# main_module.net
KiCad netlist of a schematic drawn in EAGLE
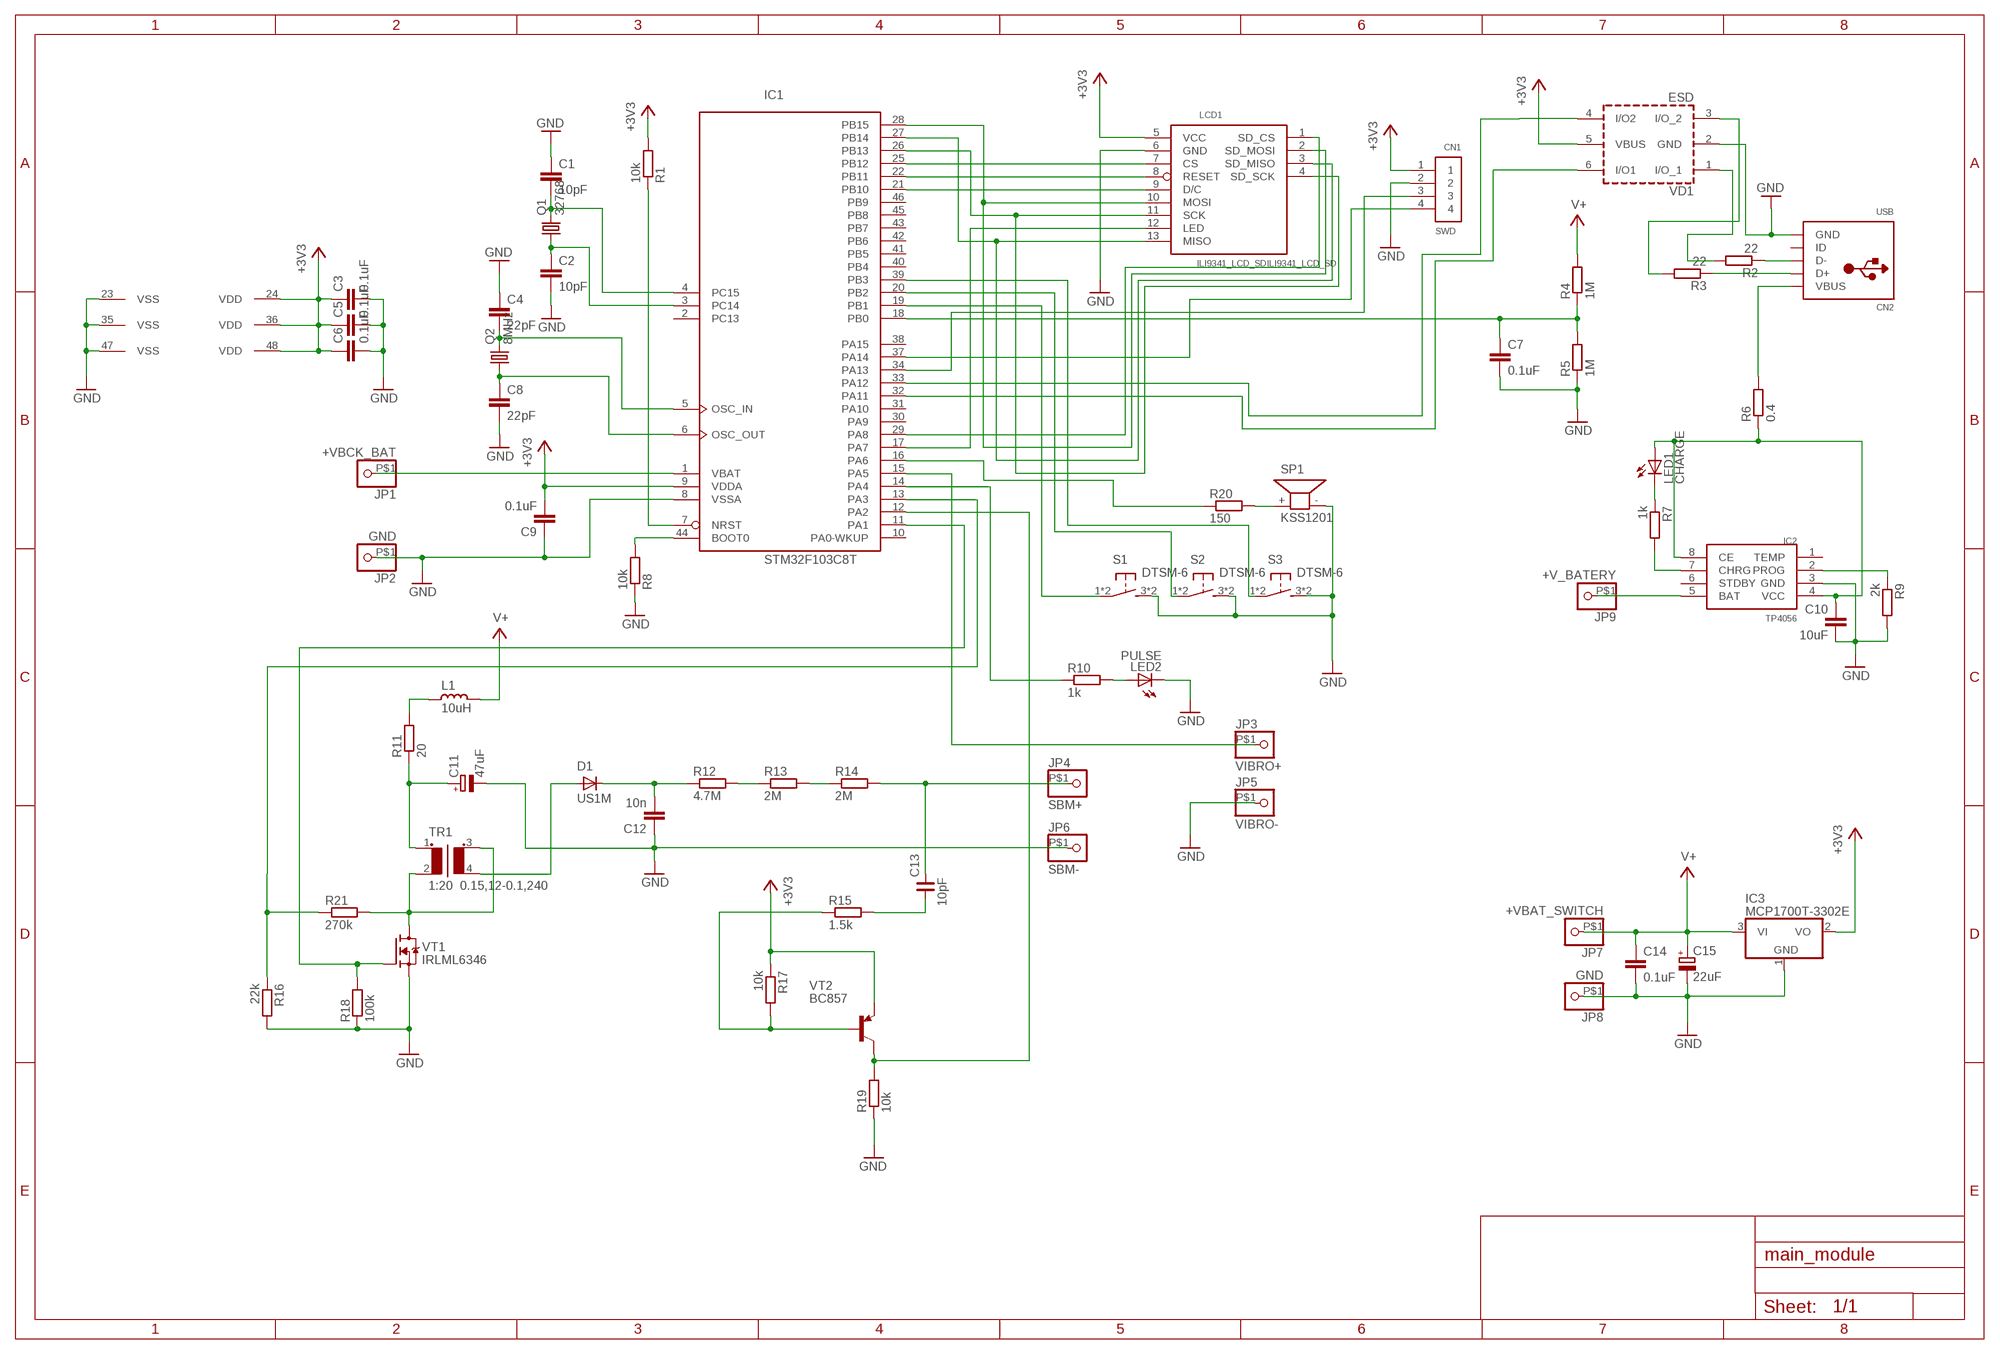
[diagram p0: schematic, sheet 1]

(export (version "E")
  (design (tool "Eeschema 10.0.6"))
  (components
    (comp (ref "C1")
      (value "10pF")
      (footprint "eagle-import:C0805")
      (libsource (lib "eagle-import") (part "C-EUC0805"))
    )
    (comp (ref "C2")
      (value "10pF")
      (footprint "eagle-import:C0805")
      (libsource (lib "eagle-import") (part "C-EUC0805"))
    )
    (comp (ref "C3")
      (value "0.1uF")
      (footprint "eagle-import:C0805")
      (libsource (lib "eagle-import") (part "C-EUC0805"))
    )
    (comp (ref "C4")
      (value "22pF")
      (footprint "eagle-import:C0805")
      (libsource (lib "eagle-import") (part "C-EUC0805"))
    )
    (comp (ref "C5")
      (value "0.1uF")
      (footprint "eagle-import:C0805")
      (libsource (lib "eagle-import") (part "C-EUC0805"))
    )
    (comp (ref "C6")
      (value "0.1uF")
      (footprint "eagle-import:C0805")
      (libsource (lib "eagle-import") (part "C-EUC0805"))
    )
    (comp (ref "C7")
      (value "0.1uF")
      (footprint "eagle-import:C0805")
      (libsource (lib "eagle-import") (part "C-EUC0805"))
    )
    (comp (ref "C8")
      (value "22pF")
      (footprint "eagle-import:C0805")
      (libsource (lib "eagle-import") (part "C-EUC0805"))
    )
    (comp (ref "C9")
      (value "0.1uF")
      (footprint "eagle-import:C0805")
      (libsource (lib "eagle-import") (part "C-EUC0805"))
    )
    (comp (ref "C10")
      (value "10uF")
      (footprint "eagle-import:C0805")
      (libsource (lib "eagle-import") (part "C-EUC0805"))
    )
    (comp (ref "C11")
      (value "47uF")
      (footprint "eagle-import:C_6032-28R")
      (libsource (lib "eagle-import") (part "CPOL-EUC/6032-28R"))
    )
    (comp (ref "C12")
      (value "10n")
      (footprint "eagle-import:C1206")
      (libsource (lib "eagle-import") (part "C-EUC1206"))
    )
    (comp (ref "C13")
      (value "10pF")
      (footprint "eagle-import:C1206")
      (libsource (lib "eagle-import") (part "C_1206"))
    )
    (comp (ref "C14")
      (value "0.1uF")
      (footprint "eagle-import:C0805")
      (libsource (lib "eagle-import") (part "C-EUC0805"))
    )
    (comp (ref "C15")
      (value "22uF")
      (footprint "eagle-import:C_6032-28R")
      (libsource (lib "eagle-import") (part "CPOL-EUC/6032-28R"))
    )
    (comp (ref "CN1")
      (value "SWD")
      (footprint "eagle-import:1X04-BIG")
      (libsource (lib "eagle-import") (part "1X4-BIG"))
    )
    (comp (ref "CN2")
      (value "USB")
      (footprint "eagle-import:USB-MINIB")
      (libsource (lib "eagle-import") (part "USBMINIB"))
    )
    (comp (ref "D1")
      (value "US1M")
      (footprint "eagle-import:SMA-DO214AC")
      (libsource (lib "eagle-import") (part "GF1"))
    )
    (comp (ref "IC1")
      (value "STM32F103C8T")
      (footprint "eagle-import:LQFP48")
      (libsource (lib "eagle-import") (part "STM32F103CT8"))
    )
    (comp (ref "IC2")
      (value "TP4056")
      (footprint "eagle-import:SOP-8")
      (libsource (lib "eagle-import") (part "TP4056"))
    )
    (comp (ref "IC3")
      (value "MCP1700T-3302E")
      (footprint "eagle-import:SOT23")
      (libsource (lib "eagle-import") (part "MCP1703CB"))
    )
    (comp (ref "JP1")
      (value "+VBCK_BAT")
      (footprint "eagle-import:1X1-BIGPOGO")
      (libsource (lib "eagle-import") (part "PINHD-1X1-BIGPOGO"))
    )
    (comp (ref "JP2")
      (value "GND")
      (footprint "eagle-import:1X1-BIGPOGO")
      (libsource (lib "eagle-import") (part "PINHD-1X1-BIGPOGO"))
    )
    (comp (ref "JP3")
      (value "VIBRO+")
      (footprint "eagle-import:1X1-BIGPOGO")
      (libsource (lib "eagle-import") (part "PINHD-1X1-BIGPOGO"))
    )
    (comp (ref "JP4")
      (value "SBM+")
      (footprint "eagle-import:1X1-BIGPOGO")
      (libsource (lib "eagle-import") (part "PINHD-1X1-BIGPOGO"))
    )
    (comp (ref "JP5")
      (value "VIBRO-")
      (footprint "eagle-import:1X1-BIGPOGO")
      (libsource (lib "eagle-import") (part "PINHD-1X1-BIGPOGO"))
    )
    (comp (ref "JP6")
      (value "SBM-")
      (footprint "eagle-import:1X1-BIGPOGO")
      (libsource (lib "eagle-import") (part "PINHD-1X1-BIGPOGO"))
    )
    (comp (ref "JP7")
      (value "+VBAT_SWITCH")
      (footprint "eagle-import:1X1-BIGPOGO")
      (libsource (lib "eagle-import") (part "PINHD-1X1-BIGPOGO"))
    )
    (comp (ref "JP8")
      (value "GND")
      (footprint "eagle-import:1X1-BIGPOGO")
      (libsource (lib "eagle-import") (part "PINHD-1X1-BIGPOGO"))
    )
    (comp (ref "JP9")
      (value "+V_BATERY")
      (footprint "eagle-import:1X1-BIGPOGO")
      (libsource (lib "eagle-import") (part "PINHD-1X1-BIGPOGO"))
    )
    (comp (ref "L1")
      (value "10uH")
      (footprint "eagle-import:L0805")
      (libsource (lib "eagle-import") (part "L_0805"))
    )
    (comp (ref "LCD1")
      (value "ILI9341_LCD_SDILI9341_LCD_SD")
      (footprint "eagle-import:ILI9341_LCD_SD")
      (libsource (lib "eagle-import") (part "ILI9341_LCD_SDILI9341_LCD_SD"))
    )
    (comp (ref "LED1")
      (value "CHARGE")
      (footprint "eagle-import:CHIP-LED0805")
      (libsource (lib "eagle-import") (part "led_LEDCHIP-LED0805"))
    )
    (comp (ref "LED2")
      (value "PULSE")
      (footprint "eagle-import:LED3MM")
      (libsource (lib "eagle-import") (part "LED3MM"))
    )
    (comp (ref "Q1")
      (value "32768")
      (footprint "eagle-import:HC49_S")
      (libsource (lib "eagle-import") (part "CRYSTALHC49S"))
    )
    (comp (ref "Q2")
      (value "8MHz")
      (footprint "eagle-import:HC49_S")
      (libsource (lib "eagle-import") (part "CRYSTALHC49S"))
    )
    (comp (ref "R1")
      (value "10k")
      (footprint "eagle-import:M0805")
      (libsource (lib "eagle-import") (part "R-EU_M0805"))
    )
    (comp (ref "R2")
      (value "22")
      (footprint "eagle-import:M0805")
      (libsource (lib "eagle-import") (part "R-EU_M0805"))
    )
    (comp (ref "R3")
      (value "22")
      (footprint "eagle-import:M0805")
      (libsource (lib "eagle-import") (part "R-EU_M0805"))
    )
    (comp (ref "R4")
      (value "1M")
      (footprint "eagle-import:M0805")
      (libsource (lib "eagle-import") (part "R-EU_M0805"))
    )
    (comp (ref "R5")
      (value "1M")
      (footprint "eagle-import:M0805")
      (libsource (lib "eagle-import") (part "R-EU_M0805"))
    )
    (comp (ref "R6")
      (value "0.4")
      (footprint "eagle-import:M1206")
      (libsource (lib "eagle-import") (part "R-EU_M1206"))
    )
    (comp (ref "R7")
      (value "1k")
      (footprint "eagle-import:M0805")
      (libsource (lib "eagle-import") (part "R-EU_M0805"))
    )
    (comp (ref "R8")
      (value "10k")
      (footprint "eagle-import:M0805")
      (libsource (lib "eagle-import") (part "R-EU_M0805"))
    )
    (comp (ref "R9")
      (value "2k")
      (footprint "eagle-import:M0805")
      (libsource (lib "eagle-import") (part "R-EU_M0805"))
    )
    (comp (ref "R10")
      (value "1k")
      (footprint "eagle-import:M0805")
      (libsource (lib "eagle-import") (part "R-EU_M0805"))
    )
    (comp (ref "R11")
      (value "20")
      (footprint "eagle-import:M0805")
      (libsource (lib "eagle-import") (part "R-EU_M0805"))
    )
    (comp (ref "R12")
      (value "4.7M")
      (footprint "eagle-import:M0805")
      (libsource (lib "eagle-import") (part "R-EU_M0805"))
    )
    (comp (ref "R13")
      (value "2M")
      (footprint "eagle-import:M0805")
      (libsource (lib "eagle-import") (part "R-EU_M0805"))
    )
    (comp (ref "R14")
      (value "2M")
      (footprint "eagle-import:M0805")
      (libsource (lib "eagle-import") (part "R-EU_M0805"))
    )
    (comp (ref "R15")
      (value "1.5k")
      (footprint "eagle-import:M0805")
      (libsource (lib "eagle-import") (part "R-EU_M0805"))
    )
    (comp (ref "R16")
      (value "22k")
      (footprint "eagle-import:M0805")
      (libsource (lib "eagle-import") (part "R-EU_M0805"))
    )
    (comp (ref "R17")
      (value "10k")
      (footprint "eagle-import:M0805")
      (libsource (lib "eagle-import") (part "R-EU_M0805"))
    )
    (comp (ref "R18")
      (value "100k")
      (footprint "eagle-import:M0805")
      (libsource (lib "eagle-import") (part "R-EU_M0805"))
    )
    (comp (ref "R19")
      (value "10k")
      (footprint "eagle-import:M0805")
      (libsource (lib "eagle-import") (part "R-EU_M0805"))
    )
    (comp (ref "R20")
      (value "150")
      (footprint "eagle-import:M0805")
      (libsource (lib "eagle-import") (part "R-EU_M0805"))
    )
    (comp (ref "R21")
      (value "270k")
      (footprint "eagle-import:M0805")
      (libsource (lib "eagle-import") (part "R-EU_M0805"))
    )
    (comp (ref "S1")
      (value "DTSM-6")
      (footprint "eagle-import:DTSM-6")
      (libsource (lib "eagle-import") (part "DTSM-6"))
    )
    (comp (ref "S2")
      (value "DTSM-6")
      (footprint "eagle-import:DTSM-6")
      (libsource (lib "eagle-import") (part "DTSM-6"))
    )
    (comp (ref "S3")
      (value "DTSM-6")
      (footprint "eagle-import:DTSM-6")
      (libsource (lib "eagle-import") (part "DTSM-6"))
    )
    (comp (ref "SP1")
      (value "KSS1201")
      (footprint "eagle-import:KSS1201")
      (libsource (lib "eagle-import") (part "KSS1201"))
    )
    (comp (ref "TR1")
      (value "1:20 0.15,12-0.1,240")
      (footprint "eagle-import:RING-TRANS")
      (libsource (lib "eagle-import") (part "RING-TRANS"))
    )
    (comp (ref "VD1")
      (value "ESD")
      (footprint "eagle-import:SOT-23-6L")
      (libsource (lib "eagle-import") (part "USBLC6-2SC6"))
    )
    (comp (ref "VT1")
      (value "IRLML6346")
      (footprint "eagle-import:SOT23")
      (libsource (lib "eagle-import") (part "MOSFET-N-SOT23"))
    )
    (comp (ref "VT2")
      (value "BC857")
      (footprint "eagle-import:SOT23-BCE")
      (libsource (lib "eagle-import") (part "-PNP-SOT23-BCE"))
    )
  )
  (nets
    (net (code "1") (name "+3V3") (class "Default")
      (node (ref "C3") (pin "1") (pinfunction "1_1") (pintype "passive"))
      (node (ref "C5") (pin "1") (pinfunction "1_1") (pintype "passive"))
      (node (ref "C6") (pin "1") (pinfunction "1_1") (pintype "passive"))
      (node (ref "C9") (pin "2") (pinfunction "2_2") (pintype "passive"))
      (node (ref "CN1") (pin "1") (pinfunction "1_1") (pintype "bidirectional"))
      (node (ref "IC1") (pin "24") (pinfunction "VDD_24") (pintype "power_in"))
      (node (ref "IC1") (pin "36") (pinfunction "VDD_36") (pintype "power_in"))
      (node (ref "IC1") (pin "48") (pinfunction "VDD_48") (pintype "power_in"))
      (node (ref "IC1") (pin "9") (pinfunction "VDDA_9") (pintype "power_in"))
      (node (ref "IC3") (pin "2") (pinfunction "VO_2") (pintype "passive"))
      (node (ref "LCD1") (pin "5") (pinfunction "VCC_5") (pintype "power_in"))
      (node (ref "R1") (pin "2") (pinfunction "2_2") (pintype "passive"))
      (node (ref "R17") (pin "1") (pinfunction "1_1") (pintype "passive"))
      (node (ref "VD1") (pin "5") (pinfunction "VBUS_5") (pintype "bidirectional"))
      (node (ref "VT2") (pin "E") (pinfunction "E_E") (pintype "passive"))
    )
    (net (code "2") (name "GND") (class "Default")
      (node (ref "C1") (pin "1") (pinfunction "1_1") (pintype "passive"))
      (node (ref "C10") (pin "2") (pinfunction "2_2") (pintype "passive"))
      (node (ref "C11") (pin "-") (pinfunction "-_-") (pintype "passive"))
      (node (ref "C12") (pin "1") (pinfunction "1_1") (pintype "passive"))
      (node (ref "C14") (pin "2") (pinfunction "2_2") (pintype "passive"))
      (node (ref "C15") (pin "-") (pinfunction "-_-") (pintype "passive"))
      (node (ref "C2") (pin "2") (pinfunction "2_2") (pintype "passive"))
      (node (ref "C3") (pin "2") (pinfunction "2_2") (pintype "passive"))
      (node (ref "C4") (pin "1") (pinfunction "1_1") (pintype "passive"))
      (node (ref "C5") (pin "2") (pinfunction "2_2") (pintype "passive"))
      (node (ref "C6") (pin "2") (pinfunction "2_2") (pintype "passive"))
      (node (ref "C7") (pin "2") (pinfunction "2_2") (pintype "passive"))
      (node (ref "C8") (pin "2") (pinfunction "2_2") (pintype "passive"))
      (node (ref "C9") (pin "1") (pinfunction "1_1") (pintype "passive"))
      (node (ref "CN1") (pin "2") (pinfunction "2_2") (pintype "bidirectional"))
      (node (ref "CN2") (pin "GND") (pinfunction "GND_GND") (pintype "power_in"))
      (node (ref "IC1") (pin "23") (pinfunction "VSS_23") (pintype "power_in"))
      (node (ref "IC1") (pin "35") (pinfunction "VSS_35") (pintype "power_in"))
      (node (ref "IC1") (pin "47") (pinfunction "VSS_47") (pintype "power_in"))
      (node (ref "IC1") (pin "8") (pinfunction "VSSA_8") (pintype "power_in"))
      (node (ref "IC2") (pin "3") (pinfunction "GND_3") (pintype "bidirectional"))
      (node (ref "IC3") (pin "1") (pinfunction "GND_1") (pintype "passive"))
      (node (ref "JP2") (pin "P$1") (pinfunction "1_P$1") (pintype "passive"))
      (node (ref "JP5") (pin "P$1") (pinfunction "1_P$1") (pintype "passive"))
      (node (ref "JP6") (pin "P$1") (pinfunction "1_P$1") (pintype "passive"))
      (node (ref "JP8") (pin "P$1") (pinfunction "1_P$1") (pintype "passive"))
      (node (ref "LCD1") (pin "6") (pinfunction "GND_6") (pintype "power_in"))
      (node (ref "LED2") (pin "K") (pinfunction "C_K") (pintype "passive"))
      (node (ref "R16") (pin "2") (pinfunction "2_2") (pintype "passive"))
      (node (ref "R18") (pin "1") (pinfunction "1_1") (pintype "passive"))
      (node (ref "R19") (pin "1") (pinfunction "1_1") (pintype "passive"))
      (node (ref "R5") (pin "1") (pinfunction "1_1") (pintype "passive"))
      (node (ref "R8") (pin "1") (pinfunction "1_1") (pintype "passive"))
      (node (ref "R9") (pin "2") (pinfunction "2_2") (pintype "passive"))
      (node (ref "S1") (pin "3") (pinfunction "3_3") (pintype "passive"))
      (node (ref "S1") (pin "4") (pinfunction "3_4") (pintype "passive"))
      (node (ref "S2") (pin "3") (pinfunction "3_3") (pintype "passive"))
      (node (ref "S2") (pin "4") (pinfunction "3_4") (pintype "passive"))
      (node (ref "S3") (pin "3") (pinfunction "3_3") (pintype "passive"))
      (node (ref "S3") (pin "4") (pinfunction "3_4") (pintype "passive"))
      (node (ref "SP1") (pin "-") (pinfunction "2_-") (pintype "passive"))
      (node (ref "VD1") (pin "2") (pinfunction "GND_2") (pintype "bidirectional"))
      (node (ref "VT1") (pin "2") (pinfunction "S_2") (pintype "passive"))
    )
    (net (code "3") (name "Net-(C13-Pad1)") (class "Default")
      (node (ref "C13") (pin "1") (pinfunction "1_1") (pintype "passive"))
      (node (ref "R15") (pin "2") (pinfunction "2_2") (pintype "passive"))
    )
    (net (code "4") (name "Net-(CN2-PadD+)") (class "Default")
      (node (ref "CN2") (pin "D+") (pinfunction "D+_D+") (pintype "bidirectional"))
      (node (ref "R3") (pin "1") (pinfunction "1_1") (pintype "passive"))
    )
    (net (code "5") (name "Net-(CN2-PadD-)") (class "Default")
      (node (ref "CN2") (pin "D-") (pinfunction "D-_D-") (pintype "bidirectional"))
      (node (ref "R2") (pin "1") (pinfunction "1_1") (pintype "passive"))
    )
    (net (code "6") (name "Net-(CN2-PadVBUS)") (class "Default")
      (node (ref "CN2") (pin "VBUS") (pinfunction "VBUS_VBUS") (pintype "power_in"))
      (node (ref "R6") (pin "2") (pinfunction "2_2") (pintype "passive"))
    )
    (net (code "7") (name "Net-(D1-C)") (class "Default")
      (node (ref "C12") (pin "2") (pinfunction "2_2") (pintype "passive"))
      (node (ref "D1") (pin "K") (pinfunction "C_K") (pintype "passive"))
      (node (ref "R12") (pin "1") (pinfunction "1_1") (pintype "passive"))
    )
    (net (code "8") (name "Net-(IC1A-BOOT0)") (class "Default")
      (node (ref "IC1") (pin "44") (pinfunction "BOOT0_44") (pintype "input"))
      (node (ref "R8") (pin "2") (pinfunction "2_2") (pintype "passive"))
    )
    (net (code "9") (name "Net-(IC1A-NRST)") (class "Default")
      (node (ref "IC1") (pin "7") (pinfunction "NRST_7") (pintype "bidirectional"))
      (node (ref "R1") (pin "1") (pinfunction "1_1") (pintype "passive"))
    )
    (net (code "10") (name "Net-(IC1A-OSC_IN)") (class "Default")
      (node (ref "C4") (pin "2") (pinfunction "2_2") (pintype "passive"))
      (node (ref "IC1") (pin "5") (pinfunction "OSC_IN_5") (pintype "bidirectional"))
      (node (ref "Q2") (pin "2") (pinfunction "2_2") (pintype "passive"))
    )
    (net (code "11") (name "Net-(IC1A-OSC_OUT)") (class "Default")
      (node (ref "C8") (pin "1") (pinfunction "1_1") (pintype "passive"))
      (node (ref "IC1") (pin "6") (pinfunction "OSC_OUT_6") (pintype "bidirectional"))
      (node (ref "Q2") (pin "1") (pinfunction "1_1") (pintype "passive"))
    )
    (net (code "12") (name "Net-(IC1A-PA1)") (class "Default")
      (node (ref "IC1") (pin "11") (pinfunction "PA1_11") (pintype "bidirectional"))
      (node (ref "R18") (pin "2") (pinfunction "2_2") (pintype "passive"))
      (node (ref "VT1") (pin "1") (pinfunction "G_1") (pintype "passive"))
    )
    (net (code "13") (name "Net-(IC1A-PA2)") (class "Default")
      (node (ref "IC1") (pin "12") (pinfunction "PA2_12") (pintype "bidirectional"))
      (node (ref "R19") (pin "2") (pinfunction "2_2") (pintype "passive"))
      (node (ref "VT2") (pin "C") (pinfunction "C_C") (pintype "passive"))
    )
    (net (code "14") (name "Net-(IC1A-PA3)") (class "Default")
      (node (ref "IC1") (pin "13") (pinfunction "PA3_13") (pintype "bidirectional"))
      (node (ref "R16") (pin "1") (pinfunction "1_1") (pintype "passive"))
      (node (ref "R21") (pin "1") (pinfunction "1_1") (pintype "passive"))
    )
    (net (code "15") (name "Net-(IC1A-PA4)") (class "Default")
      (node (ref "IC1") (pin "14") (pinfunction "PA4_14") (pintype "bidirectional"))
      (node (ref "R10") (pin "1") (pinfunction "1_1") (pintype "passive"))
    )
    (net (code "16") (name "Net-(IC1A-PA5)") (class "Default")
      (node (ref "IC1") (pin "15") (pinfunction "PA5_15") (pintype "bidirectional"))
      (node (ref "JP3") (pin "P$1") (pinfunction "1_P$1") (pintype "passive"))
    )
    (net (code "17") (name "Net-(IC1A-PA6)") (class "Default")
      (node (ref "IC1") (pin "16") (pinfunction "PA6_16") (pintype "bidirectional"))
      (node (ref "R20") (pin "1") (pinfunction "1_1") (pintype "passive"))
    )
    (net (code "18") (name "Net-(IC1A-PA7)") (class "Default")
      (node (ref "IC1") (pin "17") (pinfunction "PA7_17") (pintype "bidirectional"))
      (node (ref "LCD1") (pin "12") (pinfunction "LED_12") (pintype "input"))
    )
    (net (code "19") (name "Net-(IC1A-PA8)") (class "Default")
      (node (ref "IC1") (pin "29") (pinfunction "PA8_29") (pintype "bidirectional"))
      (node (ref "LCD1") (pin "1") (pinfunction "SD_CS_1") (pintype "input"))
    )
    (net (code "20") (name "Net-(IC1A-PA11)") (class "Default")
      (node (ref "IC1") (pin "32") (pinfunction "PA11_32") (pintype "bidirectional"))
      (node (ref "VD1") (pin "6") (pinfunction "I/O1_6") (pintype "bidirectional"))
    )
    (net (code "21") (name "Net-(IC1A-PA12)") (class "Default")
      (node (ref "IC1") (pin "33") (pinfunction "PA12_33") (pintype "bidirectional"))
      (node (ref "VD1") (pin "4") (pinfunction "I/O2_4") (pintype "bidirectional"))
    )
    (net (code "22") (name "Net-(IC1A-PA13)") (class "Default")
      (node (ref "CN1") (pin "3") (pinfunction "3_3") (pintype "bidirectional"))
      (node (ref "IC1") (pin "34") (pinfunction "PA13_34") (pintype "bidirectional"))
    )
    (net (code "23") (name "Net-(IC1A-PA14)") (class "Default")
      (node (ref "CN1") (pin "4") (pinfunction "4_4") (pintype "bidirectional"))
      (node (ref "IC1") (pin "37") (pinfunction "PA14_37") (pintype "bidirectional"))
    )
    (net (code "24") (name "Net-(IC1A-PB0)") (class "Default")
      (node (ref "C7") (pin "1") (pinfunction "1_1") (pintype "passive"))
      (node (ref "IC1") (pin "18") (pinfunction "PB0_18") (pintype "bidirectional"))
      (node (ref "R4") (pin "1") (pinfunction "1_1") (pintype "passive"))
      (node (ref "R5") (pin "2") (pinfunction "2_2") (pintype "passive"))
    )
    (net (code "25") (name "Net-(IC1A-PB1)") (class "Default")
      (node (ref "IC1") (pin "19") (pinfunction "PB1_19") (pintype "bidirectional"))
      (node (ref "S1") (pin "1") (pinfunction "1_1") (pintype "passive"))
      (node (ref "S1") (pin "2") (pinfunction "1_2") (pintype "passive"))
    )
    (net (code "26") (name "Net-(IC1A-PB2)") (class "Default")
      (node (ref "IC1") (pin "20") (pinfunction "PB2_20") (pintype "bidirectional"))
      (node (ref "S2") (pin "1") (pinfunction "1_1") (pintype "passive"))
      (node (ref "S2") (pin "2") (pinfunction "1_2") (pintype "passive"))
    )
    (net (code "27") (name "Net-(IC1A-PB3)") (class "Default")
      (node (ref "IC1") (pin "39") (pinfunction "PB3_39") (pintype "bidirectional"))
      (node (ref "S3") (pin "1") (pinfunction "1_1") (pintype "passive"))
      (node (ref "S3") (pin "2") (pinfunction "1_2") (pintype "passive"))
    )
    (net (code "28") (name "Net-(IC1A-PB10)") (class "Default")
      (node (ref "IC1") (pin "21") (pinfunction "PB10_21") (pintype "bidirectional"))
      (node (ref "LCD1") (pin "9") (pinfunction "D/C_9") (pintype "input"))
    )
    (net (code "29") (name "Net-(IC1A-PB11)") (class "Default")
      (node (ref "IC1") (pin "22") (pinfunction "PB11_22") (pintype "bidirectional"))
      (node (ref "LCD1") (pin "8") (pinfunction "RESET_8") (pintype "input"))
    )
    (net (code "30") (name "Net-(IC1A-PB12)") (class "Default")
      (node (ref "IC1") (pin "25") (pinfunction "PB12_25") (pintype "bidirectional"))
      (node (ref "LCD1") (pin "7") (pinfunction "CS_7") (pintype "input"))
    )
    (net (code "31") (name "Net-(IC1A-PB13)") (class "Default")
      (node (ref "IC1") (pin "26") (pinfunction "PB13_26") (pintype "bidirectional"))
      (node (ref "LCD1") (pin "11") (pinfunction "SCK_11") (pintype "input"))
      (node (ref "LCD1") (pin "4") (pinfunction "SD_SCK_4") (pintype "input"))
    )
    (net (code "32") (name "Net-(IC1A-PB14)") (class "Default")
      (node (ref "IC1") (pin "27") (pinfunction "PB14_27") (pintype "bidirectional"))
      (node (ref "LCD1") (pin "13") (pinfunction "MISO_13") (pintype "bidirectional"))
      (node (ref "LCD1") (pin "3") (pinfunction "SD_MISO_3") (pintype "bidirectional"))
    )
    (net (code "33") (name "Net-(IC1A-PB15)") (class "Default")
      (node (ref "IC1") (pin "28") (pinfunction "PB15_28") (pintype "bidirectional"))
      (node (ref "LCD1") (pin "10") (pinfunction "MOSI_10") (pintype "bidirectional"))
      (node (ref "LCD1") (pin "2") (pinfunction "SD_MOSI_2") (pintype "bidirectional"))
    )
    (net (code "34") (name "Net-(IC1A-PC14)") (class "Default")
      (node (ref "C2") (pin "1") (pinfunction "1_1") (pintype "passive"))
      (node (ref "IC1") (pin "3") (pinfunction "PC14_3") (pintype "bidirectional"))
      (node (ref "Q1") (pin "1") (pinfunction "1_1") (pintype "passive"))
    )
    (net (code "35") (name "Net-(IC1A-PC15)") (class "Default")
      (node (ref "C1") (pin "2") (pinfunction "2_2") (pintype "passive"))
      (node (ref "IC1") (pin "4") (pinfunction "PC15_4") (pintype "bidirectional"))
      (node (ref "Q1") (pin "2") (pinfunction "2_2") (pintype "passive"))
    )
    (net (code "36") (name "Net-(IC1A-VBAT)") (class "Default")
      (node (ref "IC1") (pin "1") (pinfunction "VBAT_1") (pintype "power_in"))
      (node (ref "JP1") (pin "P$1") (pinfunction "1_P$1") (pintype "passive"))
    )
    (net (code "37") (name "Net-(IC2-BAT)") (class "Default")
      (node (ref "IC2") (pin "5") (pinfunction "BAT_5") (pintype "bidirectional"))
      (node (ref "JP9") (pin "P$1") (pinfunction "1_P$1") (pintype "passive"))
    )
    (net (code "38") (name "Net-(IC2-CE)") (class "Default")
      (node (ref "C10") (pin "1") (pinfunction "1_1") (pintype "passive"))
      (node (ref "IC2") (pin "4") (pinfunction "VCC_4") (pintype "bidirectional"))
      (node (ref "IC2") (pin "8") (pinfunction "CE_8") (pintype "bidirectional"))
      (node (ref "LED1") (pin "A") (pinfunction "A_A") (pintype "passive"))
      (node (ref "R6") (pin "1") (pinfunction "1_1") (pintype "passive"))
    )
    (net (code "39") (name "Net-(IC2-CHRG)") (class "Default")
      (node (ref "IC2") (pin "7") (pinfunction "CHRG_7") (pintype "bidirectional"))
      (node (ref "R7") (pin "2") (pinfunction "2_2") (pintype "passive"))
    )
    (net (code "40") (name "Net-(IC2-PROG)") (class "Default")
      (node (ref "IC2") (pin "2") (pinfunction "PROG_2") (pintype "bidirectional"))
      (node (ref "R9") (pin "1") (pinfunction "1_1") (pintype "passive"))
    )
    (net (code "41") (name "Net-(JP4-1)") (class "Default")
      (node (ref "C13") (pin "2") (pinfunction "2_2") (pintype "passive"))
      (node (ref "JP4") (pin "P$1") (pinfunction "1_P$1") (pintype "passive"))
      (node (ref "R14") (pin "2") (pinfunction "2_2") (pintype "passive"))
    )
    (net (code "42") (name "Net-(L1-Pad2)") (class "Default")
      (node (ref "L1") (pin "2") (pinfunction "2_2") (pintype "passive"))
      (node (ref "R11") (pin "2") (pinfunction "2_2") (pintype "passive"))
    )
    (net (code "43") (name "Net-(LED1-PadC)") (class "Default")
      (node (ref "LED1") (pin "C") (pinfunction "C_C") (pintype "passive"))
      (node (ref "R7") (pin "1") (pinfunction "1_1") (pintype "passive"))
    )
    (net (code "44") (name "Net-(LED2-PadA)") (class "Default")
      (node (ref "LED2") (pin "A") (pinfunction "A_A") (pintype "passive"))
      (node (ref "R10") (pin "2") (pinfunction "2_2") (pintype "passive"))
    )
    (net (code "45") (name "Net-(R12-Pad2)") (class "Default")
      (node (ref "R12") (pin "2") (pinfunction "2_2") (pintype "passive"))
      (node (ref "R13") (pin "1") (pinfunction "1_1") (pintype "passive"))
    )
    (net (code "46") (name "Net-(R13-Pad2)") (class "Default")
      (node (ref "R13") (pin "2") (pinfunction "2_2") (pintype "passive"))
      (node (ref "R14") (pin "1") (pinfunction "1_1") (pintype "passive"))
    )
    (net (code "47") (name "Net-(R15-Pad1)") (class "Default")
      (node (ref "R15") (pin "1") (pinfunction "1_1") (pintype "passive"))
      (node (ref "R17") (pin "2") (pinfunction "2_2") (pintype "passive"))
      (node (ref "VT2") (pin "B") (pinfunction "B_B") (pintype "passive"))
    )
    (net (code "48") (name "Net-(SP1-1)") (class "Default")
      (node (ref "R20") (pin "2") (pinfunction "2_2") (pintype "passive"))
      (node (ref "SP1") (pin "+") (pinfunction "1_+") (pintype "passive"))
    )
    (net (code "49") (name "Net-(TR1-P1)") (class "Default")
      (node (ref "C11") (pin "+") (pinfunction "+_+") (pintype "passive"))
      (node (ref "R11") (pin "1") (pinfunction "1_1") (pintype "passive"))
      (node (ref "TR1") (pin "1") (pinfunction "P1_1") (pintype "passive"))
    )
    (net (code "50") (name "Net-(TR1-P2)") (class "Default")
      (node (ref "R21") (pin "2") (pinfunction "2_2") (pintype "passive"))
      (node (ref "TR1") (pin "2") (pinfunction "P2_2") (pintype "passive"))
      (node (ref "TR1") (pin "3") (pinfunction "S1_3") (pintype "passive"))
      (node (ref "VT1") (pin "3") (pinfunction "D_3") (pintype "passive"))
    )
    (net (code "51") (name "Net-(TR1-S2)") (class "Default")
      (node (ref "D1") (pin "A") (pinfunction "A_A") (pintype "passive"))
      (node (ref "TR1") (pin "4") (pinfunction "S2_4") (pintype "passive"))
    )
    (net (code "52") (name "Net-(VD1-I{slash}O_1)") (class "Default")
      (node (ref "R2") (pin "2") (pinfunction "2_2") (pintype "passive"))
      (node (ref "VD1") (pin "1") (pinfunction "I/O_1_1") (pintype "bidirectional"))
    )
    (net (code "53") (name "Net-(VD1-I{slash}O_2)") (class "Default")
      (node (ref "R3") (pin "2") (pinfunction "2_2") (pintype "passive"))
      (node (ref "VD1") (pin "3") (pinfunction "I/O_2_3") (pintype "bidirectional"))
    )
    (net (code "54") (name "V+") (class "Default")
      (node (ref "C14") (pin "1") (pinfunction "1_1") (pintype "passive"))
      (node (ref "C15") (pin "+") (pinfunction "+_+") (pintype "passive"))
      (node (ref "IC3") (pin "3") (pinfunction "VI_3") (pintype "input"))
      (node (ref "JP7") (pin "P$1") (pinfunction "1_P$1") (pintype "passive"))
      (node (ref "L1") (pin "1") (pinfunction "1_1") (pintype "passive"))
      (node (ref "R4") (pin "2") (pinfunction "2_2") (pintype "passive"))
    )
    (net (code "55") (name "unconnected-(CN2-PadID)") (class "Default")
      (node (ref "CN2") (pin "ID") (pinfunction "ID_ID") (pintype "bidirectional"))
    )
    (net (code "56") (name "unconnected-(IC1A-PA0-WKUP-Pad10)") (class "Default")
      (node (ref "IC1") (pin "10") (pinfunction "PA0-WKUP_10") (pintype "bidirectional"))
    )
    (net (code "57") (name "unconnected-(IC1A-PA9-Pad30)") (class "Default")
      (node (ref "IC1") (pin "30") (pinfunction "PA9_30") (pintype "bidirectional"))
    )
    (net (code "58") (name "unconnected-(IC1A-PA10-Pad31)") (class "Default")
      (node (ref "IC1") (pin "31") (pinfunction "PA10_31") (pintype "bidirectional"))
    )
    (net (code "59") (name "unconnected-(IC1A-PA15-Pad38)") (class "Default")
      (node (ref "IC1") (pin "38") (pinfunction "PA15_38") (pintype "bidirectional"))
    )
    (net (code "60") (name "unconnected-(IC1A-PB4-Pad40)") (class "Default")
      (node (ref "IC1") (pin "40") (pinfunction "PB4_40") (pintype "bidirectional"))
    )
    (net (code "61") (name "unconnected-(IC1A-PB5-Pad41)") (class "Default")
      (node (ref "IC1") (pin "41") (pinfunction "PB5_41") (pintype "bidirectional"))
    )
    (net (code "62") (name "unconnected-(IC1A-PB6-Pad42)") (class "Default")
      (node (ref "IC1") (pin "42") (pinfunction "PB6_42") (pintype "bidirectional"))
    )
    (net (code "63") (name "unconnected-(IC1A-PB7-Pad43)") (class "Default")
      (node (ref "IC1") (pin "43") (pinfunction "PB7_43") (pintype "bidirectional"))
    )
    (net (code "64") (name "unconnected-(IC1A-PB8-Pad45)") (class "Default")
      (node (ref "IC1") (pin "45") (pinfunction "PB8_45") (pintype "bidirectional"))
    )
    (net (code "65") (name "unconnected-(IC1A-PB9-Pad46)") (class "Default")
      (node (ref "IC1") (pin "46") (pinfunction "PB9_46") (pintype "bidirectional"))
    )
    (net (code "66") (name "unconnected-(IC1A-PC13-Pad2)") (class "Default")
      (node (ref "IC1") (pin "2") (pinfunction "PC13_2") (pintype "bidirectional"))
    )
    (net (code "67") (name "unconnected-(IC2-STDBY-Pad6)") (class "Default")
      (node (ref "IC2") (pin "6") (pinfunction "STDBY_6") (pintype "bidirectional"))
    )
    (net (code "68") (name "unconnected-(IC2-TEMP-Pad1)") (class "Default")
      (node (ref "IC2") (pin "1") (pinfunction "TEMP_1") (pintype "bidirectional"))
    )
  )
)
